# Ad8232_placa_V4.net
KiCad netlist of a schematic drawn in EAGLE
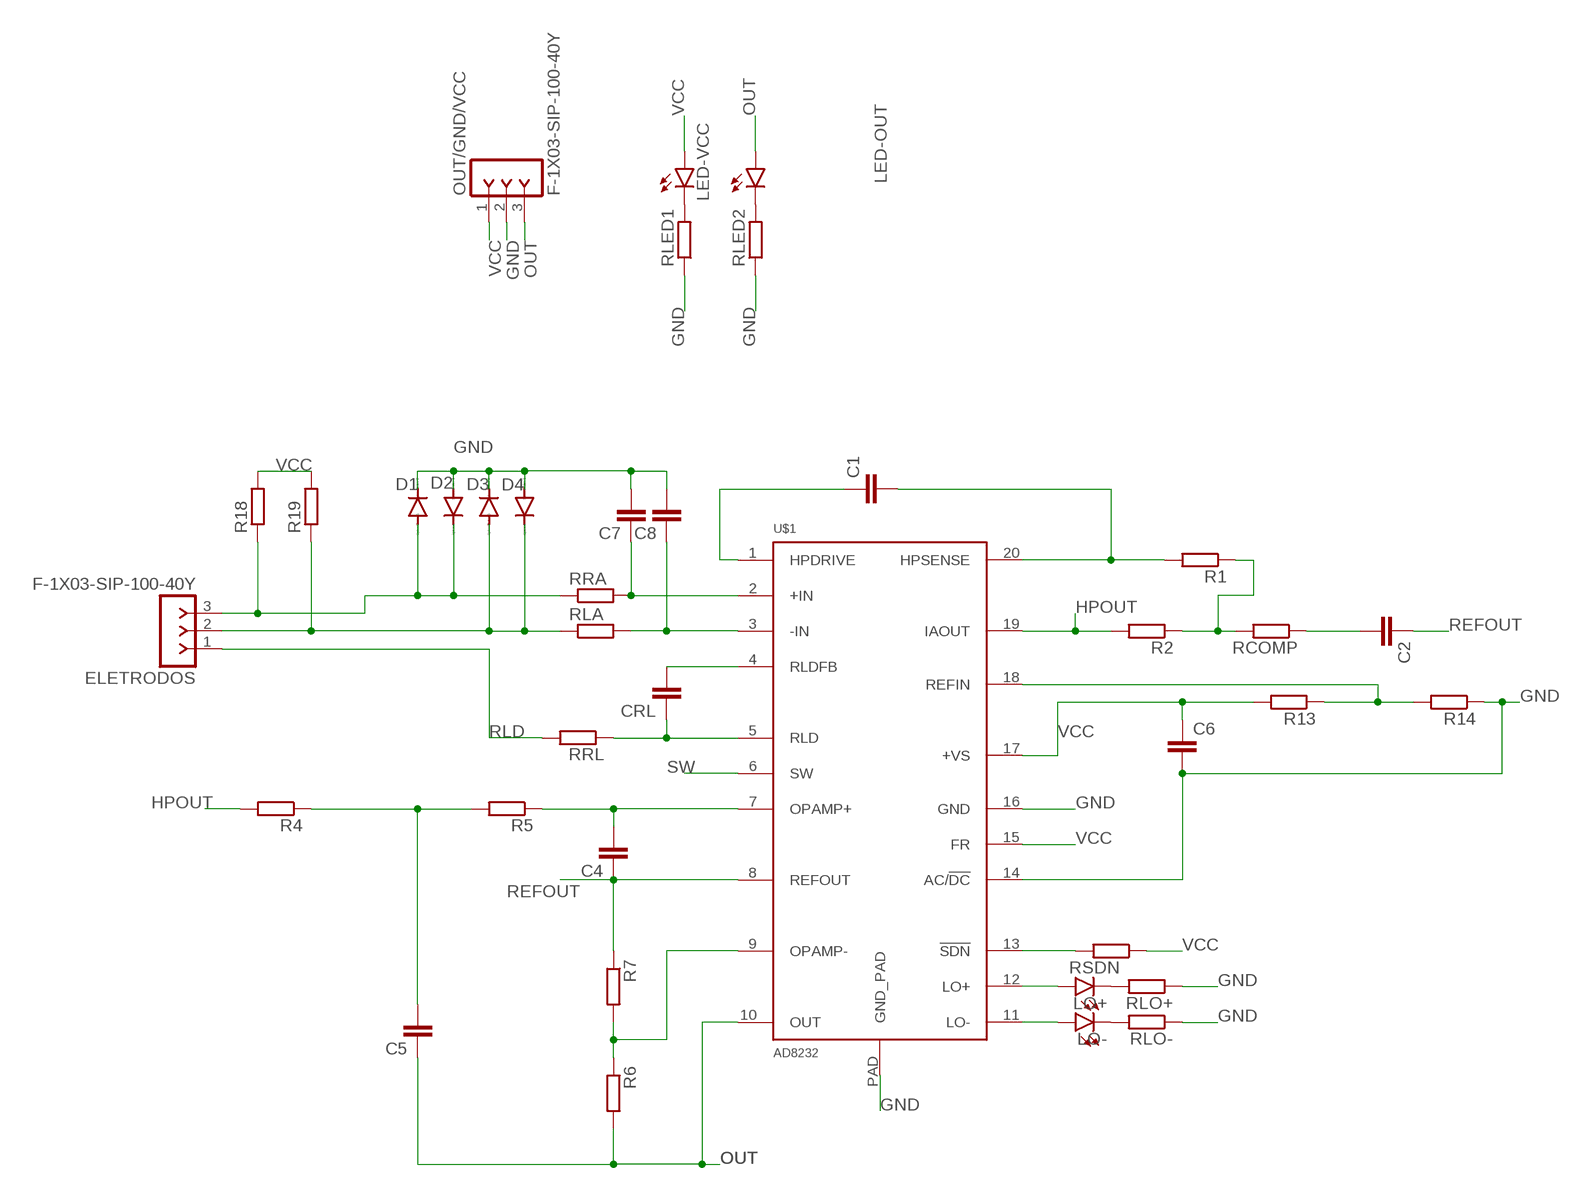
[diagram p0: schematic, sheet 1]

(export (version "E")
  (design (tool "Eeschema 10.0.6"))
  (components
    (comp (ref "C1")
      (value "C-EUC0805")
      (footprint "eagle-import:C0805")
      (libsource (lib "eagle-import") (part "C-EUC0805"))
    )
    (comp (ref "C2")
      (value "C-EUC0805")
      (footprint "eagle-import:C0805")
      (libsource (lib "eagle-import") (part "C-EUC0805"))
    )
    (comp (ref "C4")
      (value "C-EUC0805")
      (footprint "eagle-import:C0805")
      (libsource (lib "eagle-import") (part "C-EUC0805"))
    )
    (comp (ref "C5")
      (value "C-EUC0805")
      (footprint "eagle-import:C0805")
      (libsource (lib "eagle-import") (part "C-EUC0805"))
    )
    (comp (ref "C6")
      (value "C-EUC0805")
      (footprint "eagle-import:C0805")
      (libsource (lib "eagle-import") (part "C-EUC0805"))
    )
    (comp (ref "C7")
      (value "C-EUC0805")
      (footprint "eagle-import:C0805")
      (libsource (lib "eagle-import") (part "C-EUC0805"))
    )
    (comp (ref "C8")
      (value "C-EUC0805")
      (footprint "eagle-import:C0805")
      (libsource (lib "eagle-import") (part "C-EUC0805"))
    )
    (comp (ref "CRL")
      (value "C-EUC0805")
      (footprint "eagle-import:C0805")
      (libsource (lib "eagle-import") (part "C-EUC0805"))
    )
    (comp (ref "D1")
      (value "DIODE-MINIMELF")
      (footprint "eagle-import:MINIMELF")
      (libsource (lib "eagle-import") (part "DIODE-MINIMELF"))
    )
    (comp (ref "D2")
      (value "DIODE-MINIMELF")
      (footprint "eagle-import:MINIMELF")
      (libsource (lib "eagle-import") (part "DIODE-MINIMELF"))
    )
    (comp (ref "D3")
      (value "DIODE-MINIMELF")
      (footprint "eagle-import:MINIMELF")
      (libsource (lib "eagle-import") (part "DIODE-MINIMELF"))
    )
    (comp (ref "D4")
      (value "DIODE-MINIMELF")
      (footprint "eagle-import:MINIMELF")
      (libsource (lib "eagle-import") (part "DIODE-MINIMELF"))
    )
    (comp (ref "ELETRODOS")
      (value "F-1X03-SIP-100-40Y")
      (footprint "eagle-import:SIP-100-03-40Y")
      (libsource (lib "eagle-import") (part "F-1X03-SIP-100-40Y"))
    )
    (comp (ref "LED-OUT")
      (value "LEDCHIPLED_0603")
      (footprint "eagle-import:CHIPLED_0603")
      (libsource (lib "eagle-import") (part "LEDCHIPLED_0603"))
    )
    (comp (ref "LED-VCC")
      (value "LEDCHIPLED_0603")
      (footprint "eagle-import:CHIPLED_0603")
      (libsource (lib "eagle-import") (part "LEDCHIPLED_0603"))
    )
    (comp (ref "LO+")
      (value "LEDCHIPLED_0603")
      (footprint "eagle-import:CHIPLED_0603")
      (libsource (lib "eagle-import") (part "LEDCHIPLED_0603"))
    )
    (comp (ref "LO-")
      (value "LEDCHIPLED_0603")
      (footprint "eagle-import:CHIPLED_0603")
      (libsource (lib "eagle-import") (part "LEDCHIPLED_0603"))
    )
    (comp (ref "OUT/GND/VCC")
      (value "F-1X03-SIP-100-40Y")
      (footprint "eagle-import:SIP-100-03-40Y")
      (libsource (lib "eagle-import") (part "F-1X03-SIP-100-40Y"))
    )
    (comp (ref "R1")
      (value "R-EU_R0805")
      (footprint "eagle-import:R0805")
      (libsource (lib "eagle-import") (part "R-EU_R0805"))
    )
    (comp (ref "R2")
      (value "R-EU_R0805")
      (footprint "eagle-import:R0805")
      (libsource (lib "eagle-import") (part "R-EU_R0805"))
    )
    (comp (ref "R4")
      (value "R-EU_R0805")
      (footprint "eagle-import:R0805")
      (libsource (lib "eagle-import") (part "R-EU_R0805"))
    )
    (comp (ref "R5")
      (value "R-EU_R0805")
      (footprint "eagle-import:R0805")
      (libsource (lib "eagle-import") (part "R-EU_R0805"))
    )
    (comp (ref "R6")
      (value "R-EU_R0805")
      (footprint "eagle-import:R0805")
      (libsource (lib "eagle-import") (part "R-EU_R0805"))
    )
    (comp (ref "R7")
      (value "R-EU_R0805")
      (footprint "eagle-import:R0805")
      (libsource (lib "eagle-import") (part "R-EU_R0805"))
    )
    (comp (ref "R13")
      (value "R-EU_R0805")
      (footprint "eagle-import:R0805")
      (libsource (lib "eagle-import") (part "R-EU_R0805"))
    )
    (comp (ref "R14")
      (value "R-EU_R0805")
      (footprint "eagle-import:R0805")
      (libsource (lib "eagle-import") (part "R-EU_R0805"))
    )
    (comp (ref "R18")
      (value "R-EU_R0805")
      (footprint "eagle-import:R0805")
      (libsource (lib "eagle-import") (part "R-EU_R0805"))
    )
    (comp (ref "R19")
      (value "R-EU_R0805")
      (footprint "eagle-import:R0805")
      (libsource (lib "eagle-import") (part "R-EU_R0805"))
    )
    (comp (ref "RCOMP")
      (value "R-EU_R0805")
      (footprint "eagle-import:R0805")
      (libsource (lib "eagle-import") (part "R-EU_R0805"))
    )
    (comp (ref "RLA")
      (value "R-EU_R0805")
      (footprint "eagle-import:R0805")
      (libsource (lib "eagle-import") (part "R-EU_R0805"))
    )
    (comp (ref "RLED1")
      (value "R-EU_R0805")
      (footprint "eagle-import:R0805")
      (libsource (lib "eagle-import") (part "R-EU_R0805"))
    )
    (comp (ref "RLED2")
      (value "R-EU_R0805")
      (footprint "eagle-import:R0805")
      (libsource (lib "eagle-import") (part "R-EU_R0805"))
    )
    (comp (ref "RLO+")
      (value "R-EU_R0805")
      (footprint "eagle-import:R0805")
      (libsource (lib "eagle-import") (part "R-EU_R0805"))
    )
    (comp (ref "RLO-")
      (value "R-EU_R0805")
      (footprint "eagle-import:R0805")
      (libsource (lib "eagle-import") (part "R-EU_R0805"))
    )
    (comp (ref "RRA")
      (value "R-EU_R0805")
      (footprint "eagle-import:R0805")
      (libsource (lib "eagle-import") (part "R-EU_R0805"))
    )
    (comp (ref "RRL")
      (value "R-EU_R0805")
      (footprint "eagle-import:R0805")
      (libsource (lib "eagle-import") (part "R-EU_R0805"))
    )
    (comp (ref "RSDN")
      (value "R-EU_R0805")
      (footprint "eagle-import:R0805")
      (libsource (lib "eagle-import") (part "R-EU_R0805"))
    )
    (comp (ref "U$1")
      (value "AD8232")
      (footprint "eagle-import:LFCSP_20")
      (fields (field (name "MF") "Analog Devices"))
      (libsource (lib "eagle-import") (part "AD8232"))
    )
  )
  (nets
    (net (code "1") (name "/GND") (class "Default")
      (node (ref "C6") (pin "2") (pinfunction "2_2") (pintype "passive"))
      (node (ref "C7") (pin "2") (pinfunction "2_2") (pintype "passive"))
      (node (ref "C8") (pin "2") (pinfunction "2_2") (pintype "passive"))
      (node (ref "D1") (pin "C") (pinfunction "C_C") (pintype "passive"))
      (node (ref "D2") (pin "A") (pinfunction "A_A") (pintype "passive"))
      (node (ref "D3") (pin "C") (pinfunction "C_C") (pintype "passive"))
      (node (ref "D4") (pin "A") (pinfunction "A_A") (pintype "passive"))
      (node (ref "OUT/GND/VCC") (pin "2") (pinfunction "2_2") (pintype "passive"))
      (node (ref "R14") (pin "1") (pinfunction "1_1") (pintype "passive"))
      (node (ref "RLED1") (pin "1") (pinfunction "1_1") (pintype "passive"))
      (node (ref "RLED2") (pin "1") (pinfunction "1_1") (pintype "passive"))
      (node (ref "RLO+") (pin "1") (pinfunction "1_1") (pintype "passive"))
      (node (ref "RLO-") (pin "1") (pinfunction "1_1") (pintype "passive"))
      (node (ref "U$1") (pin "14") (pinfunction "AC/~{DC}_14") (pintype "bidirectional"))
      (node (ref "U$1") (pin "16") (pinfunction "GND_16") (pintype "bidirectional"))
      (node (ref "U$1") (pin "PAD") (pinfunction "GND_PAD_PAD") (pintype "bidirectional"))
    )
    (net (code "2") (name "/HPOUT") (class "Default")
      (node (ref "R2") (pin "2") (pinfunction "2_2") (pintype "passive"))
      (node (ref "R4") (pin "2") (pinfunction "2_2") (pintype "passive"))
      (node (ref "U$1") (pin "19") (pinfunction "IAOUT_19") (pintype "bidirectional"))
    )
    (net (code "3") (name "/OUT") (class "Default")
      (node (ref "C5") (pin "1") (pinfunction "1_1") (pintype "passive"))
      (node (ref "LED-OUT") (pin "A") (pinfunction "A_A") (pintype "passive"))
      (node (ref "OUT/GND/VCC") (pin "3") (pinfunction "3_3") (pintype "passive"))
      (node (ref "R6") (pin "2") (pinfunction "2_2") (pintype "passive"))
      (node (ref "U$1") (pin "10") (pinfunction "OUT_10") (pintype "bidirectional"))
    )
    (net (code "4") (name "/REFOUT") (class "Default")
      (node (ref "C2") (pin "1") (pinfunction "1_1") (pintype "passive"))
      (node (ref "C4") (pin "1") (pinfunction "1_1") (pintype "passive"))
      (node (ref "R7") (pin "1") (pinfunction "1_1") (pintype "passive"))
      (node (ref "U$1") (pin "8") (pinfunction "REFOUT_8") (pintype "bidirectional"))
    )
    (net (code "5") (name "/RLD") (class "Default")
      (node (ref "ELETRODOS") (pin "1") (pinfunction "1_1") (pintype "passive"))
      (node (ref "RRL") (pin "2") (pinfunction "2_2") (pintype "passive"))
    )
    (net (code "6") (name "/SW") (class "Default")
      (node (ref "C2") (pin "2") (pinfunction "2_2") (pintype "passive"))
      (node (ref "RCOMP") (pin "1") (pinfunction "1_1") (pintype "passive"))
      (node (ref "U$1") (pin "6") (pinfunction "SW_6") (pintype "bidirectional"))
    )
    (net (code "7") (name "/VCC") (class "Default")
      (node (ref "C6") (pin "1") (pinfunction "1_1") (pintype "passive"))
      (node (ref "LED-VCC") (pin "A") (pinfunction "A_A") (pintype "passive"))
      (node (ref "OUT/GND/VCC") (pin "1") (pinfunction "1_1") (pintype "passive"))
      (node (ref "R13") (pin "2") (pinfunction "2_2") (pintype "passive"))
      (node (ref "R18") (pin "2") (pinfunction "2_2") (pintype "passive"))
      (node (ref "R19") (pin "2") (pinfunction "2_2") (pintype "passive"))
      (node (ref "RSDN") (pin "1") (pinfunction "1_1") (pintype "passive"))
      (node (ref "U$1") (pin "15") (pinfunction "FR_15") (pintype "bidirectional"))
      (node (ref "U$1") (pin "17") (pinfunction "+VS_17") (pintype "bidirectional"))
    )
    (net (code "8") (name "Net-(C5-Pad2)") (class "Default")
      (node (ref "C5") (pin "2") (pinfunction "2_2") (pintype "passive"))
      (node (ref "R4") (pin "1") (pinfunction "1_1") (pintype "passive"))
      (node (ref "R5") (pin "2") (pinfunction "2_2") (pintype "passive"))
    )
    (net (code "9") (name "Net-(D1-PadA)") (class "Default")
      (node (ref "D1") (pin "A") (pinfunction "A_A") (pintype "passive"))
      (node (ref "D2") (pin "C") (pinfunction "C_C") (pintype "passive"))
      (node (ref "ELETRODOS") (pin "3") (pinfunction "3_3") (pintype "passive"))
      (node (ref "R18") (pin "1") (pinfunction "1_1") (pintype "passive"))
      (node (ref "RRA") (pin "1") (pinfunction "1_1") (pintype "passive"))
    )
    (net (code "10") (name "Net-(D3-PadA)") (class "Default")
      (node (ref "D3") (pin "A") (pinfunction "A_A") (pintype "passive"))
      (node (ref "D4") (pin "C") (pinfunction "C_C") (pintype "passive"))
      (node (ref "ELETRODOS") (pin "2") (pinfunction "2_2") (pintype "passive"))
      (node (ref "R19") (pin "1") (pinfunction "1_1") (pintype "passive"))
      (node (ref "RLA") (pin "1") (pinfunction "1_1") (pintype "passive"))
    )
    (net (code "11") (name "Net-(LED-OUT-PadC)") (class "Default")
      (node (ref "LED-OUT") (pin "C") (pinfunction "C_C") (pintype "passive"))
      (node (ref "RLED2") (pin "2") (pinfunction "2_2") (pintype "passive"))
    )
    (net (code "12") (name "Net-(LED-VCC-PadC)") (class "Default")
      (node (ref "LED-VCC") (pin "C") (pinfunction "C_C") (pintype "passive"))
      (node (ref "RLED1") (pin "2") (pinfunction "2_2") (pintype "passive"))
    )
    (net (code "13") (name "Net-(LO+-PadC)") (class "Default")
      (node (ref "LO+") (pin "C") (pinfunction "C_C") (pintype "passive"))
      (node (ref "RLO+") (pin "2") (pinfunction "2_2") (pintype "passive"))
    )
    (net (code "14") (name "Net-(LO--PadC)") (class "Default")
      (node (ref "LO-") (pin "C") (pinfunction "C_C") (pintype "passive"))
      (node (ref "RLO-") (pin "2") (pinfunction "2_2") (pintype "passive"))
    )
    (net (code "15") (name "Net-(R1-Pad1)") (class "Default")
      (node (ref "R1") (pin "1") (pinfunction "1_1") (pintype "passive"))
      (node (ref "R2") (pin "1") (pinfunction "1_1") (pintype "passive"))
      (node (ref "RCOMP") (pin "2") (pinfunction "2_2") (pintype "passive"))
    )
    (net (code "16") (name "Net-(U$1-+IN)") (class "Default")
      (node (ref "C7") (pin "1") (pinfunction "1_1") (pintype "passive"))
      (node (ref "RRA") (pin "2") (pinfunction "2_2") (pintype "passive"))
      (node (ref "U$1") (pin "2") (pinfunction "+IN_2") (pintype "bidirectional"))
    )
    (net (code "17") (name "Net-(U$1--IN)") (class "Default")
      (node (ref "C8") (pin "1") (pinfunction "1_1") (pintype "passive"))
      (node (ref "RLA") (pin "2") (pinfunction "2_2") (pintype "passive"))
      (node (ref "U$1") (pin "3") (pinfunction "-IN_3") (pintype "bidirectional"))
    )
    (net (code "18") (name "Net-(U$1-HPDRIVE)") (class "Default")
      (node (ref "C1") (pin "1") (pinfunction "1_1") (pintype "passive"))
      (node (ref "U$1") (pin "1") (pinfunction "HPDRIVE_1") (pintype "bidirectional"))
    )
    (net (code "19") (name "Net-(U$1-HPSENSE)") (class "Default")
      (node (ref "C1") (pin "2") (pinfunction "2_2") (pintype "passive"))
      (node (ref "R1") (pin "2") (pinfunction "2_2") (pintype "passive"))
      (node (ref "U$1") (pin "20") (pinfunction "HPSENSE_20") (pintype "bidirectional"))
    )
    (net (code "20") (name "Net-(U$1-LO+)") (class "Default")
      (node (ref "LO+") (pin "A") (pinfunction "A_A") (pintype "passive"))
      (node (ref "U$1") (pin "12") (pinfunction "LO+_12") (pintype "bidirectional"))
    )
    (net (code "21") (name "Net-(U$1-LO-)") (class "Default")
      (node (ref "LO-") (pin "A") (pinfunction "A_A") (pintype "passive"))
      (node (ref "U$1") (pin "11") (pinfunction "LO-_11") (pintype "bidirectional"))
    )
    (net (code "22") (name "Net-(U$1-OPAMP+)") (class "Default")
      (node (ref "C4") (pin "2") (pinfunction "2_2") (pintype "passive"))
      (node (ref "R5") (pin "1") (pinfunction "1_1") (pintype "passive"))
      (node (ref "U$1") (pin "7") (pinfunction "OPAMP+_7") (pintype "bidirectional"))
    )
    (net (code "23") (name "Net-(U$1-OPAMP-)") (class "Default")
      (node (ref "R6") (pin "1") (pinfunction "1_1") (pintype "passive"))
      (node (ref "R7") (pin "2") (pinfunction "2_2") (pintype "passive"))
      (node (ref "U$1") (pin "9") (pinfunction "OPAMP-_9") (pintype "bidirectional"))
    )
    (net (code "24") (name "Net-(U$1-REFIN)") (class "Default")
      (node (ref "R13") (pin "1") (pinfunction "1_1") (pintype "passive"))
      (node (ref "R14") (pin "2") (pinfunction "2_2") (pintype "passive"))
      (node (ref "U$1") (pin "18") (pinfunction "REFIN_18") (pintype "bidirectional"))
    )
    (net (code "25") (name "Net-(U$1-RLD)") (class "Default")
      (node (ref "CRL") (pin "1") (pinfunction "1_1") (pintype "passive"))
      (node (ref "RRL") (pin "1") (pinfunction "1_1") (pintype "passive"))
      (node (ref "U$1") (pin "5") (pinfunction "RLD_5") (pintype "bidirectional"))
    )
    (net (code "26") (name "Net-(U$1-RLDFB)") (class "Default")
      (node (ref "CRL") (pin "2") (pinfunction "2_2") (pintype "passive"))
      (node (ref "U$1") (pin "4") (pinfunction "RLDFB_4") (pintype "bidirectional"))
    )
    (net (code "27") (name "Net-(U$1-~{SDN})") (class "Default")
      (node (ref "RSDN") (pin "2") (pinfunction "2_2") (pintype "passive"))
      (node (ref "U$1") (pin "13") (pinfunction "~{SDN}_13") (pintype "bidirectional"))
    )
  )
)
